# Sheet_1.net
KiCad netlist of a schematic drawn in EasyEDA
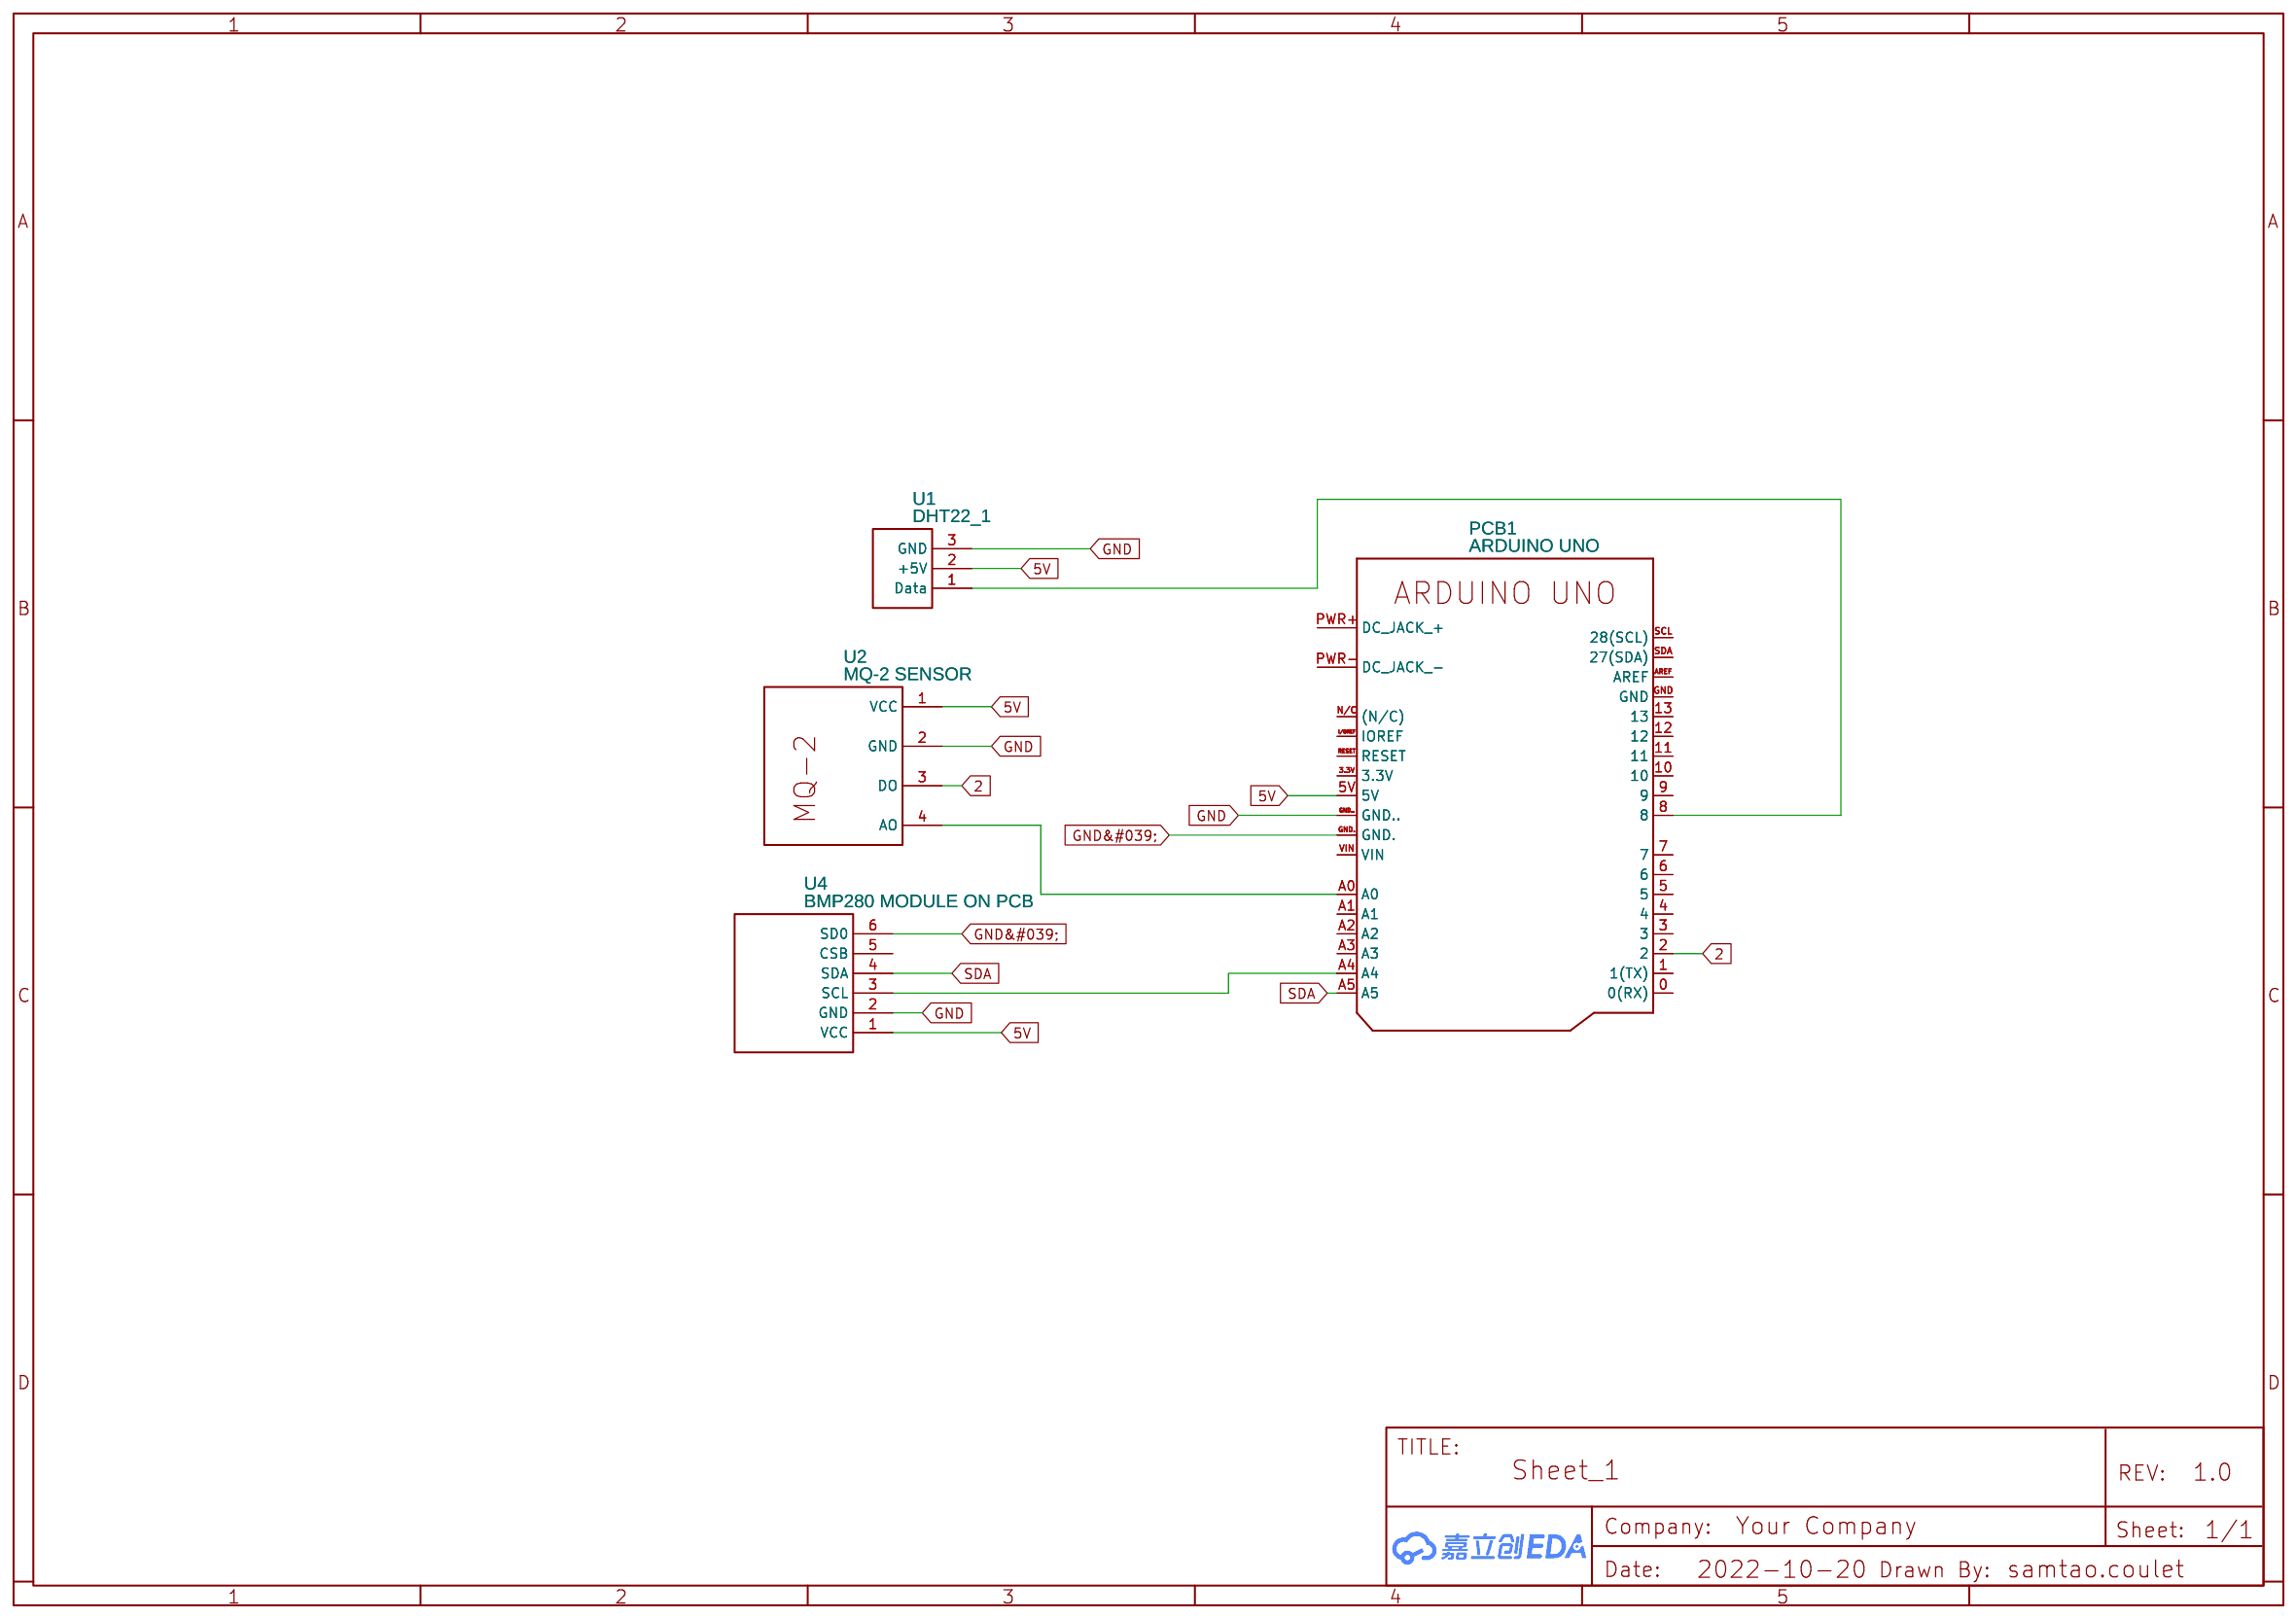
[diagram p0: schematic sheet]

(export (version "E")
  (design (tool "Eeschema 10.0.6"))
  (components
    (comp (ref "PCB1") (value "ARDUINO UNO") (libsource (lib "") (part "ARDUINO UNO")))
    (comp (ref "U1") (value "DHT22_1") (libsource (lib "") (part "DHT22_1")))
    (comp (ref "U2")
      (value "MQ-2 SENSOR")
      (fields (field (name "BOM_Supplier Part") "undefined"))
      (libsource (lib "") (part "MQ-2 SENSOR"))
    )
    (comp (ref "U4")
      (value "BMP280 MODULE ON PCB")
      (fields
        (field (name "BOM_Manufacturer Part") "BMP280 Module")
        (field (name "BOM_Supplier Part") "BMP280")
      )
      (libsource (lib "") (part "BMP280 MODULE ON PCB"))
    )
  )
  (nets
    (net (code "1") (name "2") (class "Default")
      (node (ref "PCB1") (pin "2") (pinfunction "2_2") (pintype "bidirectional"))
      (node (ref "U2") (pin "3") (pinfunction "DO_3") (pintype "unspecified"))
    )
    (net (code "2") (name "5V") (class "Default")
      (node (ref "PCB1") (pin "5V") (pinfunction "5V_5V") (pintype "bidirectional"))
      (node (ref "U1") (pin "2") (pinfunction "+5V_2") (pintype "unspecified"))
      (node (ref "U2") (pin "1") (pinfunction "VCC_1") (pintype "unspecified"))
      (node (ref "U4") (pin "1") (pinfunction "VCC_1") (pintype "unspecified"))
    )
    (net (code "3") (name "GND") (class "Default")
      (node (ref "PCB1") (pin "GND..") (pinfunction "GND.._GND..") (pintype "bidirectional"))
      (node (ref "U1") (pin "3") (pinfunction "GND_3") (pintype "unspecified"))
      (node (ref "U2") (pin "2") (pinfunction "GND_2") (pintype "unspecified"))
      (node (ref "U4") (pin "2") (pinfunction "GND_2") (pintype "unspecified"))
    )
    (net (code "4") (name "GND&#039;") (class "Default")
      (node (ref "PCB1") (pin "GND.") (pinfunction "GND._GND.") (pintype "bidirectional"))
      (node (ref "U4") (pin "6") (pinfunction "SD0_6") (pintype "unspecified"))
    )
    (net (code "5") (name "Net-(U1-Data)") (class "Default")
      (node (ref "PCB1") (pin "8") (pinfunction "8_8") (pintype "bidirectional"))
      (node (ref "U1") (pin "1") (pinfunction "Data_1") (pintype "unspecified"))
    )
    (net (code "6") (name "Net-(U2-AO)") (class "Default")
      (node (ref "PCB1") (pin "A0") (pinfunction "A0_A0") (pintype "bidirectional"))
      (node (ref "U2") (pin "4") (pinfunction "AO_4") (pintype "unspecified"))
    )
    (net (code "7") (name "Net-(U4-SCL)") (class "Default")
      (node (ref "PCB1") (pin "A4") (pinfunction "A4_A4") (pintype "bidirectional"))
      (node (ref "U4") (pin "3") (pinfunction "SCL_3") (pintype "unspecified"))
    )
    (net (code "8") (name "SDA") (class "Default")
      (node (ref "PCB1") (pin "A5") (pinfunction "A5_A5") (pintype "bidirectional"))
      (node (ref "U4") (pin "4") (pinfunction "SDA_4") (pintype "unspecified"))
    )
    (net (code "9") (name "unconnected-(PCB1-(N{slash}C)-PadN{slash}C)") (class "Default")
      (node (ref "PCB1") (pin "N/C") (pinfunction "(N/C)_N/C") (pintype "bidirectional"))
    )
    (net (code "10") (name "unconnected-(PCB1-0(RX)-Pad0)") (class "Default")
      (node (ref "PCB1") (pin "0") (pinfunction "0(RX)_0") (pintype "bidirectional"))
    )
    (net (code "11") (name "unconnected-(PCB1-1(TX)-Pad1)") (class "Default")
      (node (ref "PCB1") (pin "1") (pinfunction "1(TX)_1") (pintype "bidirectional"))
    )
    (net (code "12") (name "unconnected-(PCB1-27(SDA)-PadSDA)") (class "Default")
      (node (ref "PCB1") (pin "SDA") (pinfunction "27(SDA)_SDA") (pintype "bidirectional"))
    )
    (net (code "13") (name "unconnected-(PCB1-28(SCL)-PadSCL)") (class "Default")
      (node (ref "PCB1") (pin "SCL") (pinfunction "28(SCL)_SCL") (pintype "bidirectional"))
    )
    (net (code "14") (name "unconnected-(PCB1-DC_JACK_+-PadPWR+)") (class "Default")
      (node (ref "PCB1") (pin "PWR+") (pinfunction "DC_JACK_+_PWR+") (pintype "passive"))
    )
    (net (code "15") (name "unconnected-(PCB1-DC_JACK_--PadPWR-)") (class "Default")
      (node (ref "PCB1") (pin "PWR-") (pinfunction "DC_JACK_-_PWR-") (pintype "passive"))
    )
    (net (code "16") (name "unconnected-(PCB1-IOREF-PadI{slash}OREF)") (class "Default")
      (node (ref "PCB1") (pin "I/OREF") (pinfunction "IOREF_I/OREF") (pintype "bidirectional"))
    )
    (net (code "17") (name "unconnected-(PCB1-Pad3)") (class "Default")
      (node (ref "PCB1") (pin "3") (pinfunction "3_3") (pintype "bidirectional"))
    )
    (net (code "18") (name "unconnected-(PCB1-Pad3.3V)") (class "Default")
      (node (ref "PCB1") (pin "3.3V") (pinfunction "3.3V_3.3V") (pintype "bidirectional"))
    )
    (net (code "19") (name "unconnected-(PCB1-Pad4)") (class "Default")
      (node (ref "PCB1") (pin "4") (pinfunction "4_4") (pintype "bidirectional"))
    )
    (net (code "20") (name "unconnected-(PCB1-Pad5)") (class "Default")
      (node (ref "PCB1") (pin "5") (pinfunction "5_5") (pintype "bidirectional"))
    )
    (net (code "21") (name "unconnected-(PCB1-Pad6)") (class "Default")
      (node (ref "PCB1") (pin "6") (pinfunction "6_6") (pintype "bidirectional"))
    )
    (net (code "22") (name "unconnected-(PCB1-Pad7)") (class "Default")
      (node (ref "PCB1") (pin "7") (pinfunction "7_7") (pintype "bidirectional"))
    )
    (net (code "23") (name "unconnected-(PCB1-Pad9)") (class "Default")
      (node (ref "PCB1") (pin "9") (pinfunction "9_9") (pintype "bidirectional"))
    )
    (net (code "24") (name "unconnected-(PCB1-Pad10)") (class "Default")
      (node (ref "PCB1") (pin "10") (pinfunction "10_10") (pintype "bidirectional"))
    )
    (net (code "25") (name "unconnected-(PCB1-Pad11)") (class "Default")
      (node (ref "PCB1") (pin "11") (pinfunction "11_11") (pintype "bidirectional"))
    )
    (net (code "26") (name "unconnected-(PCB1-Pad12)") (class "Default")
      (node (ref "PCB1") (pin "12") (pinfunction "12_12") (pintype "bidirectional"))
    )
    (net (code "27") (name "unconnected-(PCB1-Pad13)") (class "Default")
      (node (ref "PCB1") (pin "13") (pinfunction "13_13") (pintype "bidirectional"))
    )
    (net (code "28") (name "unconnected-(PCB1-PadA1)") (class "Default")
      (node (ref "PCB1") (pin "A1") (pinfunction "A1_A1") (pintype "bidirectional"))
    )
    (net (code "29") (name "unconnected-(PCB1-PadA2)") (class "Default")
      (node (ref "PCB1") (pin "A2") (pinfunction "A2_A2") (pintype "bidirectional"))
    )
    (net (code "30") (name "unconnected-(PCB1-PadA3)") (class "Default")
      (node (ref "PCB1") (pin "A3") (pinfunction "A3_A3") (pintype "bidirectional"))
    )
    (net (code "31") (name "unconnected-(PCB1-PadAREF)") (class "Default")
      (node (ref "PCB1") (pin "AREF") (pinfunction "AREF_AREF") (pintype "bidirectional"))
    )
    (net (code "32") (name "unconnected-(PCB1-PadGND)") (class "Default")
      (node (ref "PCB1") (pin "GND") (pinfunction "GND_GND") (pintype "bidirectional"))
    )
    (net (code "33") (name "unconnected-(PCB1-PadRESET)") (class "Default")
      (node (ref "PCB1") (pin "RESET") (pinfunction "RESET_RESET") (pintype "bidirectional"))
    )
    (net (code "34") (name "unconnected-(PCB1-PadVIN)") (class "Default")
      (node (ref "PCB1") (pin "VIN") (pinfunction "VIN_VIN") (pintype "bidirectional"))
    )
    (net (code "35") (name "unconnected-(U4-CSB-Pad5)") (class "Default")
      (node (ref "U4") (pin "5") (pinfunction "CSB_5") (pintype "unspecified"))
    )
  )
)
